# CPLD.net
KiCad netlist of a schematic drawn in Altium Designer
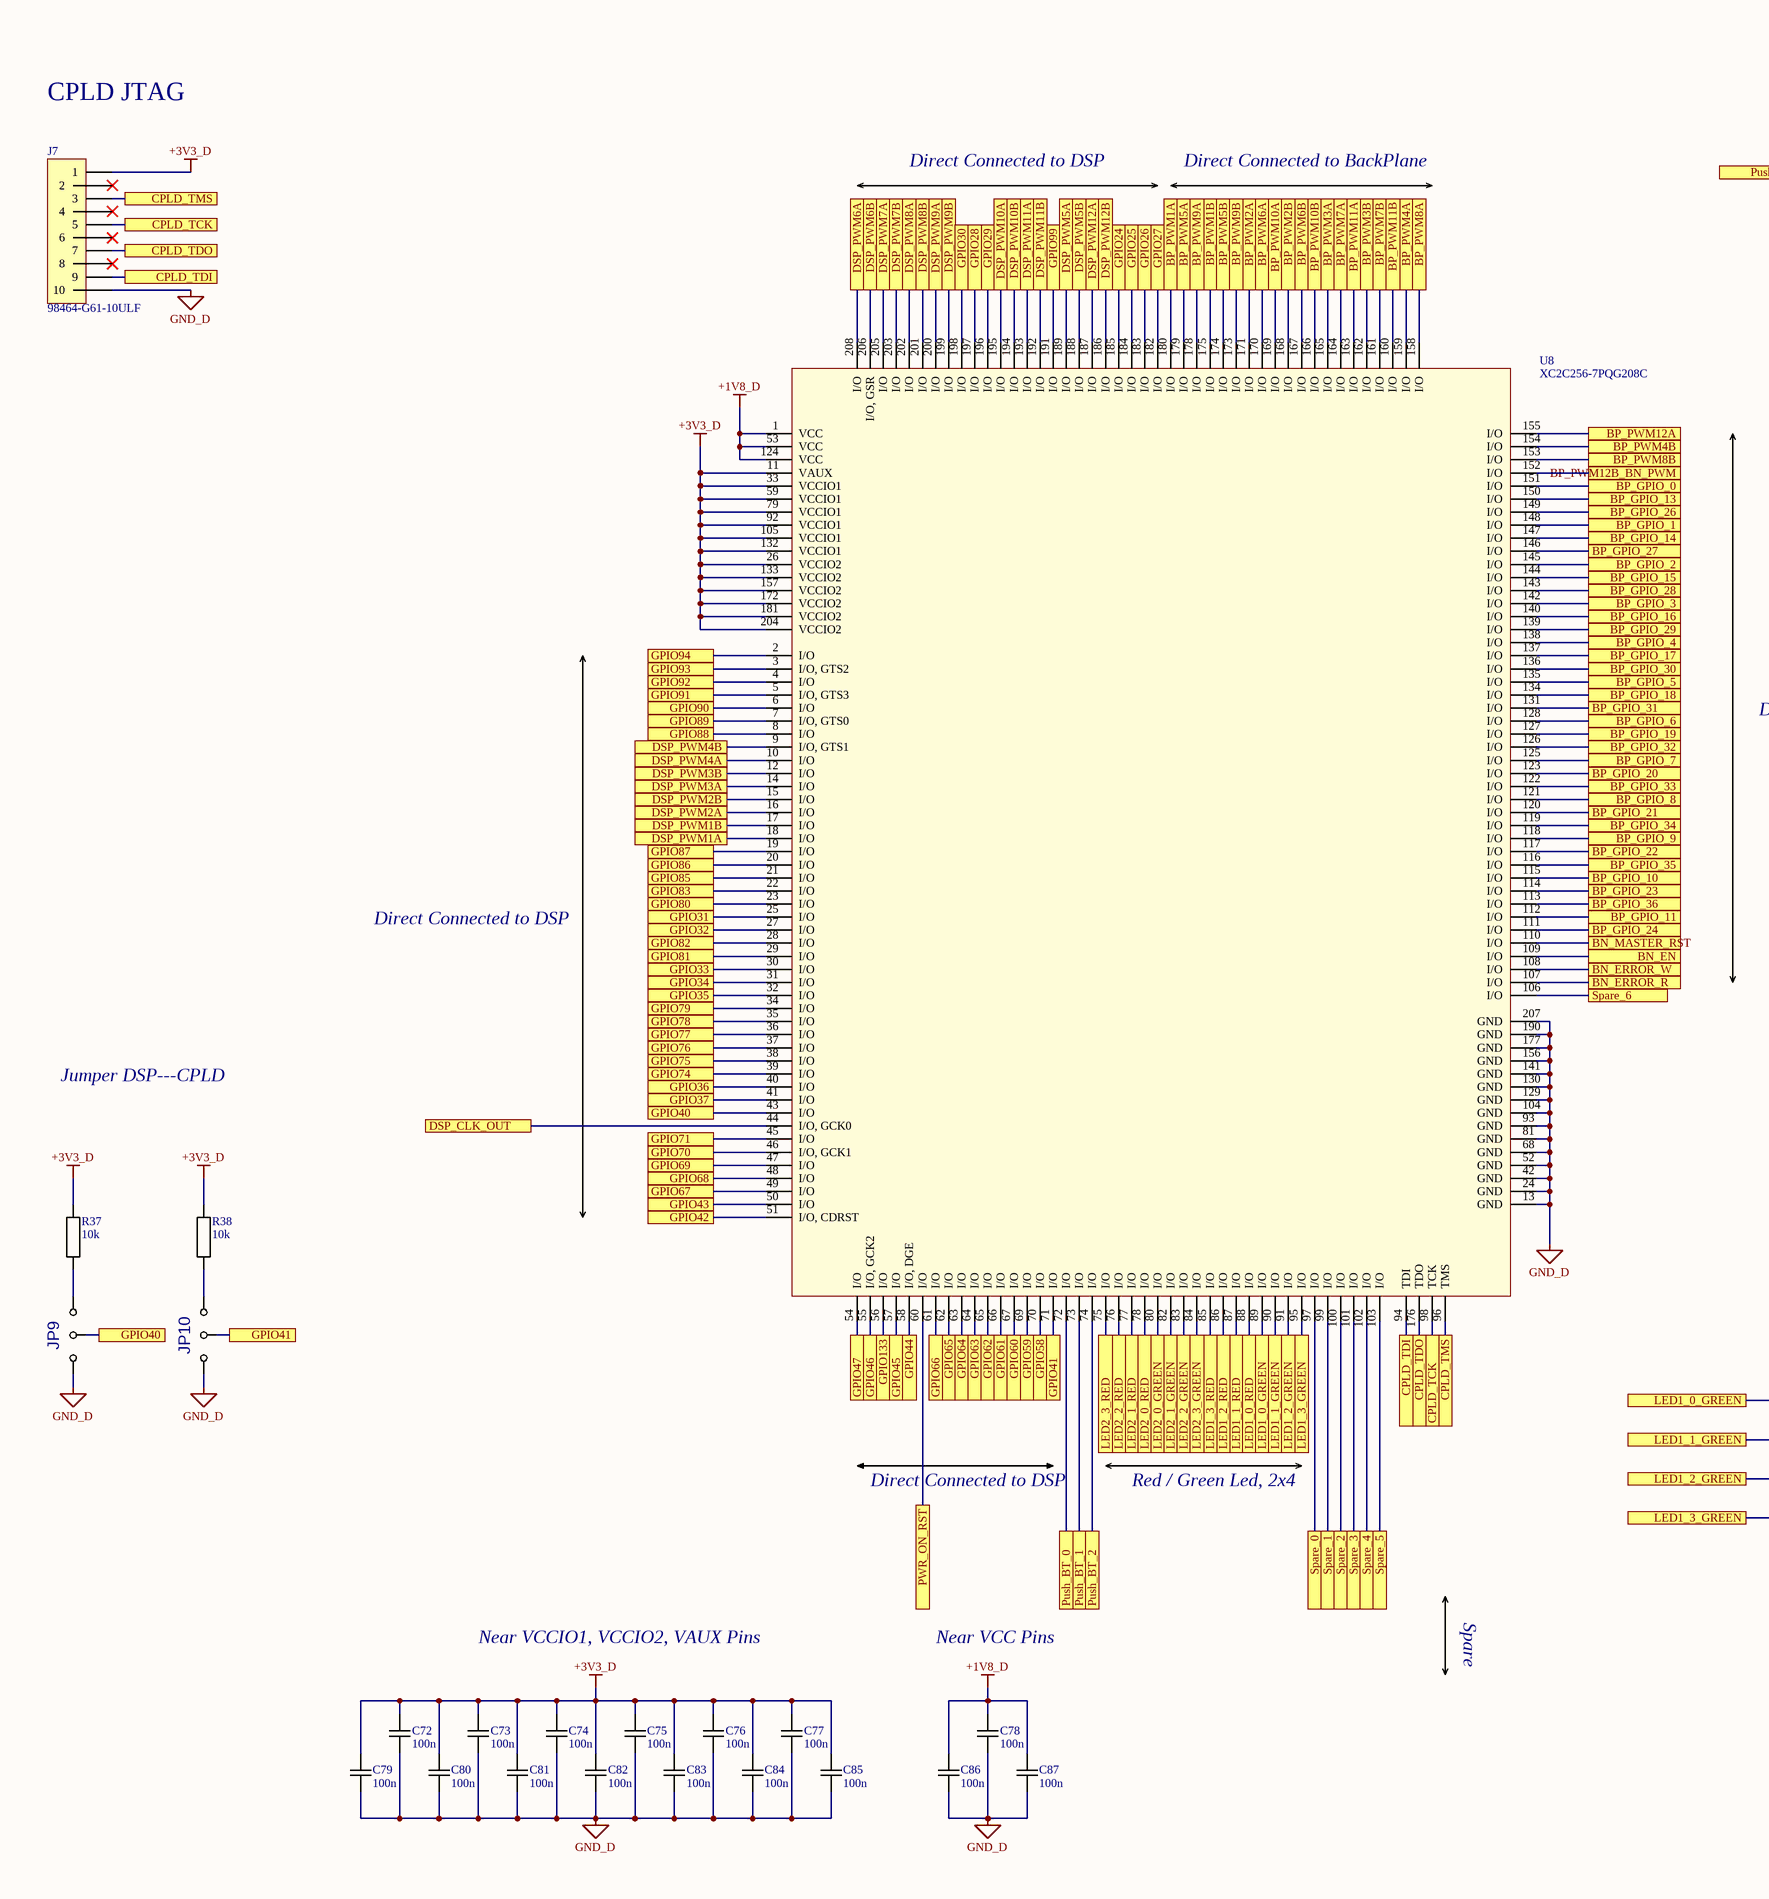
[diagram p0: CPLD.SchDoc, left]
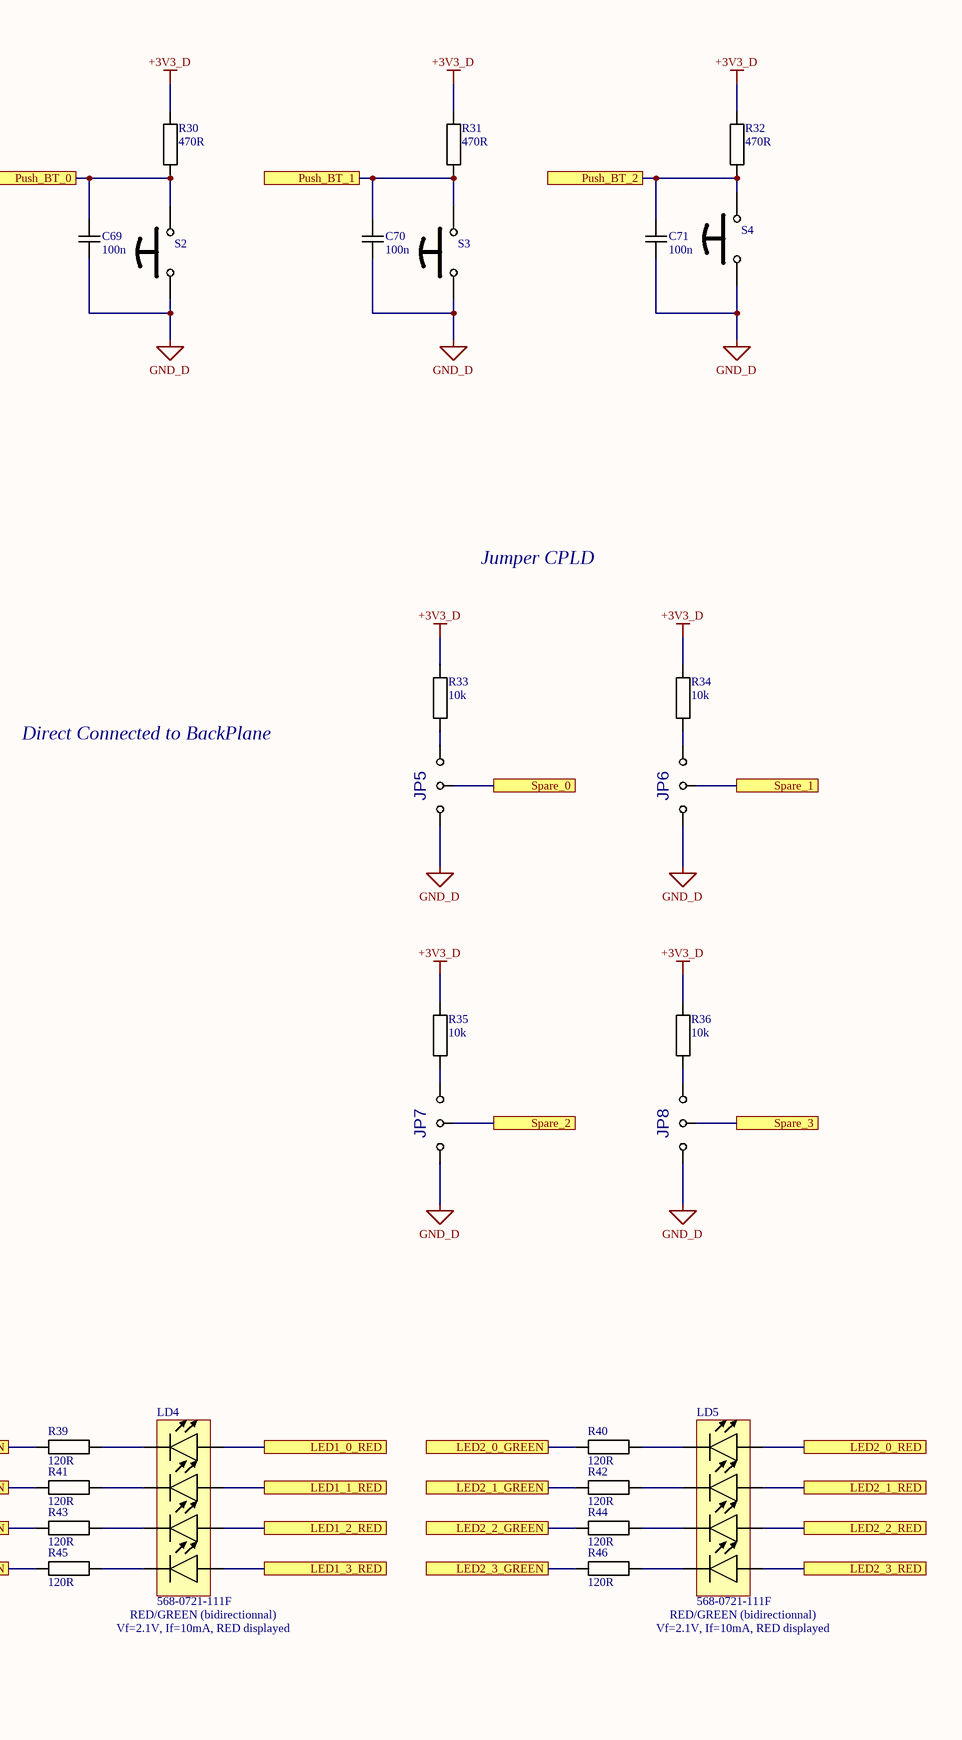
[diagram p1: CPLD.SchDoc, right]

(export (version "E")
  (design (tool "Eeschema 10.0.6"))
  (components
    (comp (ref "C69")
      (value "100n")
      (footprint "CAPACITOR 2012 REFLOW")
      (description "Capacitor X7R 10% 50V 2012(0805)")
      (libsource (lib "Capacitor") (part "Capacitor"))
    )
    (comp (ref "C70")
      (value "100n")
      (footprint "CAPACITOR 2012 REFLOW")
      (description "Capacitor X7R 10% 50V 2012(0805)")
      (libsource (lib "Capacitor") (part "Capacitor"))
    )
    (comp (ref "C71")
      (value "100n")
      (footprint "CAPACITOR 2012 REFLOW")
      (description "Capacitor X7R 10% 50V 2012(0805)")
      (libsource (lib "Capacitor") (part "Capacitor"))
    )
    (comp (ref "C72")
      (value "100n")
      (footprint "CAPACITOR 1608 REFLOW")
      (description "Capacitor X7R 10% 50V 1608(0603)")
      (libsource (lib "Capacitor") (part "Capacitor"))
    )
    (comp (ref "C73")
      (value "100n")
      (footprint "CAPACITOR 1608 REFLOW")
      (description "Capacitor X7R 10% 50V 1608(0603)")
      (libsource (lib "Capacitor") (part "Capacitor"))
    )
    (comp (ref "C74")
      (value "100n")
      (footprint "CAPACITOR 1608 REFLOW")
      (description "Capacitor X7R 10% 50V 1608(0603)")
      (libsource (lib "Capacitor") (part "Capacitor"))
    )
    (comp (ref "C75")
      (value "100n")
      (footprint "CAPACITOR 1608 REFLOW")
      (description "Capacitor X7R 10% 50V 1608(0603)")
      (libsource (lib "Capacitor") (part "Capacitor"))
    )
    (comp (ref "C76")
      (value "100n")
      (footprint "CAPACITOR 1608 REFLOW")
      (description "Capacitor X7R 10% 50V 1608(0603)")
      (libsource (lib "Capacitor") (part "Capacitor"))
    )
    (comp (ref "C77")
      (value "100n")
      (footprint "CAPACITOR 1608 REFLOW")
      (description "Capacitor X7R 10% 50V 1608(0603)")
      (libsource (lib "Capacitor") (part "Capacitor"))
    )
    (comp (ref "C78")
      (value "100n")
      (footprint "CAPACITOR 1608 REFLOW")
      (description "Capacitor X7R 10% 50V 1608(0603)")
      (libsource (lib "Capacitor") (part "Capacitor"))
    )
    (comp (ref "C79")
      (value "100n")
      (footprint "CAPACITOR 1608 REFLOW")
      (description "Capacitor X7R 10% 50V 1608(0603)")
      (libsource (lib "Capacitor") (part "Capacitor"))
    )
    (comp (ref "C80")
      (value "100n")
      (footprint "CAPACITOR 1608 REFLOW")
      (description "Capacitor X7R 10% 50V 1608(0603)")
      (libsource (lib "Capacitor") (part "Capacitor"))
    )
    (comp (ref "C81")
      (value "100n")
      (footprint "CAPACITOR 1608 REFLOW")
      (description "Capacitor X7R 10% 50V 1608(0603)")
      (libsource (lib "Capacitor") (part "Capacitor"))
    )
    (comp (ref "C82")
      (value "100n")
      (footprint "CAPACITOR 1608 REFLOW")
      (description "Capacitor X7R 10% 50V 1608(0603)")
      (libsource (lib "Capacitor") (part "Capacitor"))
    )
    (comp (ref "C83")
      (value "100n")
      (footprint "CAPACITOR 1608 REFLOW")
      (description "Capacitor X7R 10% 50V 1608(0603)")
      (libsource (lib "Capacitor") (part "Capacitor"))
    )
    (comp (ref "C84")
      (value "100n")
      (footprint "CAPACITOR 1608 REFLOW")
      (description "Capacitor X7R 10% 50V 1608(0603)")
      (libsource (lib "Capacitor") (part "Capacitor"))
    )
    (comp (ref "C85")
      (value "100n")
      (footprint "CAPACITOR 1608 REFLOW")
      (description "Capacitor X7R 10% 50V 1608(0603)")
      (libsource (lib "Capacitor") (part "Capacitor"))
    )
    (comp (ref "C86")
      (value "100n")
      (footprint "CAPACITOR 1608 REFLOW")
      (description "Capacitor X7R 10% 50V 1608(0603)")
      (libsource (lib "Capacitor") (part "Capacitor"))
    )
    (comp (ref "C87")
      (value "100n")
      (footprint "CAPACITOR 1608 REFLOW")
      (description "Capacitor X7R 10% 50V 1608(0603)")
      (libsource (lib "Capacitor") (part "Capacitor"))
    )
    (comp (ref "J7")
      (value "98464-G61-10ULF")
      (footprint "FlatCable2x5 2MM Right Angle TH FCI 98614-G61-10ULF")
      (description "FlatCable2x5")
      (fields (field (name "MANUFACTURER") "Amphenol FCI"))
      (libsource (lib "Connector") (part "FlatCable2x5"))
    )
    (comp (ref "JP5")
      (value "{Value}")
      (footprint "JUMPER3 TH")
      (description "JUMPER 3 POS")
      (libsource (lib "Jumper") (part "JUMPER 3 POS"))
    )
    (comp (ref "JP6")
      (value "{Value}")
      (footprint "JUMPER3 TH")
      (description "JUMPER 3 POS")
      (libsource (lib "Jumper") (part "JUMPER 3 POS"))
    )
    (comp (ref "JP7")
      (value "{Value}")
      (footprint "JUMPER3 TH")
      (description "JUMPER 3 POS")
      (libsource (lib "Jumper") (part "JUMPER 3 POS"))
    )
    (comp (ref "JP8")
      (value "{Value}")
      (footprint "JUMPER3 TH")
      (description "JUMPER 3 POS")
      (libsource (lib "Jumper") (part "JUMPER 3 POS"))
    )
    (comp (ref "JP9")
      (value "{Value}")
      (footprint "JUMPER3 TH")
      (description "JUMPER 3 POS")
      (libsource (lib "Jumper") (part "JUMPER 3 POS"))
    )
    (comp (ref "JP10")
      (value "{Value}")
      (footprint "JUMPER3 TH")
      (description "JUMPER 3 POS")
      (libsource (lib "Jumper") (part "JUMPER 3 POS"))
    )
    (comp (ref "LD4")
      (value "568-0721-111F")
      (footprint "LED Dialight 568-0721-111")
      (description "LED Dialight 568-0721-111F")
      (fields (field (name "MANUFACTURER") "Dialight"))
      (libsource (lib "Diode") (part "LED Dialight 568-0721-111F"))
    )
    (comp (ref "LD5")
      (value "568-0721-111F")
      (footprint "LED Dialight 568-0721-111")
      (description "LED Dialight 568-0721-111F")
      (fields (field (name "MANUFACTURER") "Dialight"))
      (libsource (lib "Diode") (part "LED Dialight 568-0721-111F"))
    )
    (comp (ref "R30")
      (value "470R")
      (footprint "RESISTOR 2012 REFLOW")
      (description "Resistor 1% 50V 125mW 2012(0805)")
      (libsource (lib "Resistor") (part "Resistor"))
    )
    (comp (ref "R31")
      (value "470R")
      (footprint "RESISTOR 2012 REFLOW")
      (description "Resistor 1% 50V 125mW 2012(0805)")
      (libsource (lib "Resistor") (part "Resistor"))
    )
    (comp (ref "R32")
      (value "470R")
      (footprint "RESISTOR 2012 REFLOW")
      (description "Resistor 1% 50V 125mW 2012(0805)")
      (libsource (lib "Resistor") (part "Resistor"))
    )
    (comp (ref "R33")
      (value "10k")
      (footprint "RESISTOR 2012 REFLOW")
      (description "Resistor 1% 50V 125mW 2012(0805)")
      (libsource (lib "Resistor") (part "Resistor"))
    )
    (comp (ref "R34")
      (value "10k")
      (footprint "RESISTOR 2012 REFLOW")
      (description "Resistor 1% 50V 125mW 2012(0805)")
      (libsource (lib "Resistor") (part "Resistor"))
    )
    (comp (ref "R35")
      (value "10k")
      (footprint "RESISTOR 2012 REFLOW")
      (description "Resistor 1% 50V 125mW 2012(0805)")
      (libsource (lib "Resistor") (part "Resistor"))
    )
    (comp (ref "R36")
      (value "10k")
      (footprint "RESISTOR 2012 REFLOW")
      (description "Resistor 1% 50V 125mW 2012(0805)")
      (libsource (lib "Resistor") (part "Resistor"))
    )
    (comp (ref "R37")
      (value "10k")
      (footprint "RESISTOR 2012 REFLOW")
      (description "Resistor 1% 50V 125mW 2012(0805)")
      (libsource (lib "Resistor") (part "Resistor"))
    )
    (comp (ref "R38")
      (value "10k")
      (footprint "RESISTOR 2012 REFLOW")
      (description "Resistor 1% 50V 125mW 2012(0805)")
      (libsource (lib "Resistor") (part "Resistor"))
    )
    (comp (ref "R39")
      (value "120R")
      (footprint "RESISTOR 1608 REFLOW")
      (description "Resistor 1% 50V 100mW 1608(0603)")
      (libsource (lib "Resistor") (part "Resistor"))
    )
    (comp (ref "R40")
      (value "120R")
      (footprint "RESISTOR 1608 REFLOW")
      (description "Resistor 1% 50V 100mW 1608(0603)")
      (libsource (lib "Resistor") (part "Resistor"))
    )
    (comp (ref "R41")
      (value "120R")
      (footprint "RESISTOR 1608 REFLOW")
      (description "Resistor 1% 50V 100mW 1608(0603)")
      (libsource (lib "Resistor") (part "Resistor"))
    )
    (comp (ref "R42")
      (value "120R")
      (footprint "RESISTOR 1608 REFLOW")
      (description "Resistor 1% 50V 100mW 1608(0603)")
      (libsource (lib "Resistor") (part "Resistor"))
    )
    (comp (ref "R43")
      (value "120R")
      (footprint "RESISTOR 1608 REFLOW")
      (description "Resistor 1% 50V 100mW 1608(0603)")
      (libsource (lib "Resistor") (part "Resistor"))
    )
    (comp (ref "R44")
      (value "120R")
      (footprint "RESISTOR 1608 REFLOW")
      (description "Resistor 1% 50V 100mW 1608(0603)")
      (libsource (lib "Resistor") (part "Resistor"))
    )
    (comp (ref "R45")
      (value "120R")
      (footprint "RESISTOR 1608 REFLOW")
      (description "Resistor 1% 50V 100mW 1608(0603)")
      (libsource (lib "Resistor") (part "Resistor"))
    )
    (comp (ref "R46")
      (value "120R")
      (footprint "RESISTOR 1608 REFLOW")
      (description "Resistor 1% 50V 100mW 1608(0603)")
      (libsource (lib "Resistor") (part "Resistor"))
    )
    (comp (ref "S2")
      (value "FSMRA4JH04")
      (footprint "Push Button C7.1x3.7 TE FSMRA4JH")
      (description "Push Button, 2 pins")
      (fields (field (name "MANUFACTURER") "TE Connectivity / Alcoswitch"))
      (libsource (lib "Button") (part "Push Button 2Pins"))
    )
    (comp (ref "S3")
      (value "FSMRA4JH04")
      (footprint "Push Button C7.1x3.7 TE FSMRA4JH")
      (description "Push Button, 2 pins")
      (fields (field (name "MANUFACTURER") "TE Connectivity / Alcoswitch"))
      (libsource (lib "Button") (part "Push Button 2Pins"))
    )
    (comp (ref "S4")
      (value "FSMRA4JH04")
      (footprint "Push Button C7.1x3.7 TE FSMRA4JH")
      (description "Push Button, 2 pins")
      (fields (field (name "MANUFACTURER") "TE Connectivity / Alcoswitch"))
      (libsource (lib "Button") (part "Push Button 2Pins"))
    )
    (comp (ref "U8")
      (value "XC2C256-7PQG208C")
      (footprint "PQFP208 P0.5 C28.0X28.0 H3.7")
      (description "XC2C256 CoolRunner-II CPLD")
      (fields (field (name "MANUFACTURER") "Xilinx"))
      (libsource (lib "Processor") (part "XC2C256-PQFP208"))
    )
  )
  (nets
    (net (code "1") (name "+1V8_D") (class "Default")
      (node (ref "C78") (pin "2") (pinfunction "2_2") (pintype "passive"))
      (node (ref "C86") (pin "2") (pinfunction "2_2") (pintype "passive"))
      (node (ref "C87") (pin "2") (pinfunction "2_2") (pintype "passive"))
      (node (ref "U8") (pin "1") (pinfunction "VCC_1") (pintype "passive"))
      (node (ref "U8") (pin "124") (pinfunction "VCC_124") (pintype "passive"))
      (node (ref "U8") (pin "53") (pinfunction "VCC_53") (pintype "passive"))
    )
    (net (code "2") (name "+3V3_D") (class "Default")
      (node (ref "C72") (pin "2") (pinfunction "2_2") (pintype "passive"))
      (node (ref "C73") (pin "2") (pinfunction "2_2") (pintype "passive"))
      (node (ref "C74") (pin "2") (pinfunction "2_2") (pintype "passive"))
      (node (ref "C75") (pin "2") (pinfunction "2_2") (pintype "passive"))
      (node (ref "C76") (pin "2") (pinfunction "2_2") (pintype "passive"))
      (node (ref "C77") (pin "2") (pinfunction "2_2") (pintype "passive"))
      (node (ref "C79") (pin "2") (pinfunction "2_2") (pintype "passive"))
      (node (ref "C80") (pin "2") (pinfunction "2_2") (pintype "passive"))
      (node (ref "C81") (pin "2") (pinfunction "2_2") (pintype "passive"))
      (node (ref "C82") (pin "2") (pinfunction "2_2") (pintype "passive"))
      (node (ref "C83") (pin "2") (pinfunction "2_2") (pintype "passive"))
      (node (ref "C84") (pin "2") (pinfunction "2_2") (pintype "passive"))
      (node (ref "C85") (pin "2") (pinfunction "2_2") (pintype "passive"))
      (node (ref "J7") (pin "1") (pinfunction "1_1") (pintype "passive"))
      (node (ref "R30") (pin "2") (pinfunction "2_2") (pintype "passive"))
      (node (ref "R31") (pin "2") (pinfunction "2_2") (pintype "passive"))
      (node (ref "R32") (pin "2") (pinfunction "2_2") (pintype "passive"))
      (node (ref "R33") (pin "2") (pinfunction "2_2") (pintype "passive"))
      (node (ref "R34") (pin "2") (pinfunction "2_2") (pintype "passive"))
      (node (ref "R35") (pin "2") (pinfunction "2_2") (pintype "passive"))
      (node (ref "R36") (pin "2") (pinfunction "2_2") (pintype "passive"))
      (node (ref "R37") (pin "1") (pinfunction "1_1") (pintype "passive"))
      (node (ref "R38") (pin "1") (pinfunction "1_1") (pintype "passive"))
      (node (ref "U8") (pin "105") (pinfunction "VCCIO1_105") (pintype "passive"))
      (node (ref "U8") (pin "11") (pinfunction "VAUX_11") (pintype "passive"))
      (node (ref "U8") (pin "132") (pinfunction "VCCIO1_132") (pintype "passive"))
      (node (ref "U8") (pin "133") (pinfunction "VCCIO2_133") (pintype "passive"))
      (node (ref "U8") (pin "157") (pinfunction "VCCIO2_157") (pintype "passive"))
      (node (ref "U8") (pin "172") (pinfunction "VCCIO2_172") (pintype "passive"))
      (node (ref "U8") (pin "181") (pinfunction "VCCIO2_181") (pintype "passive"))
      (node (ref "U8") (pin "204") (pinfunction "VCCIO2_204") (pintype "passive"))
      (node (ref "U8") (pin "26") (pinfunction "VCCIO2_26") (pintype "passive"))
      (node (ref "U8") (pin "33") (pinfunction "VCCIO1_33") (pintype "passive"))
      (node (ref "U8") (pin "59") (pinfunction "VCCIO1_59") (pintype "passive"))
      (node (ref "U8") (pin "79") (pinfunction "VCCIO1_79") (pintype "passive"))
      (node (ref "U8") (pin "92") (pinfunction "VCCIO1_92") (pintype "passive"))
    )
    (net (code "3") (name "/BN_EN") (class "Default")
      (node (ref "U8") (pin "109") (pinfunction "I/O_109") (pintype "passive"))
    )
    (net (code "4") (name "/BN_ERROR_R") (class "Default")
      (node (ref "U8") (pin "107") (pinfunction "I/O_107") (pintype "passive"))
    )
    (net (code "5") (name "/BN_ERROR_W") (class "Default")
      (node (ref "U8") (pin "108") (pinfunction "I/O_108") (pintype "passive"))
    )
    (net (code "6") (name "/BN_MASTER_RST") (class "Default")
      (node (ref "U8") (pin "110") (pinfunction "I/O_110") (pintype "passive"))
    )
    (net (code "7") (name "/BP_GPIO_0") (class "Default")
      (node (ref "U8") (pin "151") (pinfunction "I/O_151") (pintype "passive"))
    )
    (net (code "8") (name "/BP_GPIO_1") (class "Default")
      (node (ref "U8") (pin "148") (pinfunction "I/O_148") (pintype "passive"))
    )
    (net (code "9") (name "/BP_GPIO_2") (class "Default")
      (node (ref "U8") (pin "145") (pinfunction "I/O_145") (pintype "passive"))
    )
    (net (code "10") (name "/BP_GPIO_3") (class "Default")
      (node (ref "U8") (pin "142") (pinfunction "I/O_142") (pintype "passive"))
    )
    (net (code "11") (name "/BP_GPIO_4") (class "Default")
      (node (ref "U8") (pin "138") (pinfunction "I/O_138") (pintype "passive"))
    )
    (net (code "12") (name "/BP_GPIO_5") (class "Default")
      (node (ref "U8") (pin "135") (pinfunction "I/O_135") (pintype "passive"))
    )
    (net (code "13") (name "/BP_GPIO_6") (class "Default")
      (node (ref "U8") (pin "128") (pinfunction "I/O_128") (pintype "passive"))
    )
    (net (code "14") (name "/BP_GPIO_7") (class "Default")
      (node (ref "U8") (pin "125") (pinfunction "I/O_125") (pintype "passive"))
    )
    (net (code "15") (name "/BP_GPIO_8") (class "Default")
      (node (ref "U8") (pin "121") (pinfunction "I/O_121") (pintype "passive"))
    )
    (net (code "16") (name "/BP_GPIO_9") (class "Default")
      (node (ref "U8") (pin "118") (pinfunction "I/O_118") (pintype "passive"))
    )
    (net (code "17") (name "/BP_GPIO_10") (class "Default")
      (node (ref "U8") (pin "115") (pinfunction "I/O_115") (pintype "passive"))
    )
    (net (code "18") (name "/BP_GPIO_11") (class "Default")
      (node (ref "U8") (pin "112") (pinfunction "I/O_112") (pintype "passive"))
    )
    (net (code "19") (name "/BP_GPIO_13") (class "Default")
      (node (ref "U8") (pin "150") (pinfunction "I/O_150") (pintype "passive"))
    )
    (net (code "20") (name "/BP_GPIO_14") (class "Default")
      (node (ref "U8") (pin "147") (pinfunction "I/O_147") (pintype "passive"))
    )
    (net (code "21") (name "/BP_GPIO_15") (class "Default")
      (node (ref "U8") (pin "144") (pinfunction "I/O_144") (pintype "passive"))
    )
    (net (code "22") (name "/BP_GPIO_16") (class "Default")
      (node (ref "U8") (pin "140") (pinfunction "I/O_140") (pintype "passive"))
    )
    (net (code "23") (name "/BP_GPIO_17") (class "Default")
      (node (ref "U8") (pin "137") (pinfunction "I/O_137") (pintype "passive"))
    )
    (net (code "24") (name "/BP_GPIO_18") (class "Default")
      (node (ref "U8") (pin "134") (pinfunction "I/O_134") (pintype "passive"))
    )
    (net (code "25") (name "/BP_GPIO_19") (class "Default")
      (node (ref "U8") (pin "127") (pinfunction "I/O_127") (pintype "passive"))
    )
    (net (code "26") (name "/BP_GPIO_20") (class "Default")
      (node (ref "U8") (pin "123") (pinfunction "I/O_123") (pintype "passive"))
    )
    (net (code "27") (name "/BP_GPIO_21") (class "Default")
      (node (ref "U8") (pin "120") (pinfunction "I/O_120") (pintype "passive"))
    )
    (net (code "28") (name "/BP_GPIO_22") (class "Default")
      (node (ref "U8") (pin "117") (pinfunction "I/O_117") (pintype "passive"))
    )
    (net (code "29") (name "/BP_GPIO_23") (class "Default")
      (node (ref "U8") (pin "114") (pinfunction "I/O_114") (pintype "passive"))
    )
    (net (code "30") (name "/BP_GPIO_24") (class "Default")
      (node (ref "U8") (pin "111") (pinfunction "I/O_111") (pintype "passive"))
    )
    (net (code "31") (name "/BP_GPIO_26") (class "Default")
      (node (ref "U8") (pin "149") (pinfunction "I/O_149") (pintype "passive"))
    )
    (net (code "32") (name "/BP_GPIO_27") (class "Default")
      (node (ref "U8") (pin "146") (pinfunction "I/O_146") (pintype "passive"))
    )
    (net (code "33") (name "/BP_GPIO_28") (class "Default")
      (node (ref "U8") (pin "143") (pinfunction "I/O_143") (pintype "passive"))
    )
    (net (code "34") (name "/BP_GPIO_29") (class "Default")
      (node (ref "U8") (pin "139") (pinfunction "I/O_139") (pintype "passive"))
    )
    (net (code "35") (name "/BP_GPIO_30") (class "Default")
      (node (ref "U8") (pin "136") (pinfunction "I/O_136") (pintype "passive"))
    )
    (net (code "36") (name "/BP_GPIO_31") (class "Default")
      (node (ref "U8") (pin "131") (pinfunction "I/O_131") (pintype "passive"))
    )
    (net (code "37") (name "/BP_GPIO_32") (class "Default")
      (node (ref "U8") (pin "126") (pinfunction "I/O_126") (pintype "passive"))
    )
    (net (code "38") (name "/BP_GPIO_33") (class "Default")
      (node (ref "U8") (pin "122") (pinfunction "I/O_122") (pintype "passive"))
    )
    (net (code "39") (name "/BP_GPIO_34") (class "Default")
      (node (ref "U8") (pin "119") (pinfunction "I/O_119") (pintype "passive"))
    )
    (net (code "40") (name "/BP_GPIO_35") (class "Default")
      (node (ref "U8") (pin "116") (pinfunction "I/O_116") (pintype "passive"))
    )
    (net (code "41") (name "/BP_GPIO_36") (class "Default")
      (node (ref "U8") (pin "113") (pinfunction "I/O_113") (pintype "passive"))
    )
    (net (code "42") (name "/BP_PWM1A") (class "Default")
      (node (ref "U8") (pin "180") (pinfunction "I/O_180") (pintype "passive"))
    )
    (net (code "43") (name "/BP_PWM1B") (class "Default")
      (node (ref "U8") (pin "175") (pinfunction "I/O_175") (pintype "passive"))
    )
    (net (code "44") (name "/BP_PWM2A") (class "Default")
      (node (ref "U8") (pin "171") (pinfunction "I/O_171") (pintype "passive"))
    )
    (net (code "45") (name "/BP_PWM2B") (class "Default")
      (node (ref "U8") (pin "168") (pinfunction "I/O_168") (pintype "passive"))
    )
    (net (code "46") (name "/BP_PWM3A") (class "Default")
      (node (ref "U8") (pin "165") (pinfunction "I/O_165") (pintype "passive"))
    )
    (net (code "47") (name "/BP_PWM3B") (class "Default")
      (node (ref "U8") (pin "162") (pinfunction "I/O_162") (pintype "passive"))
    )
    (net (code "48") (name "/BP_PWM4A") (class "Default")
      (node (ref "U8") (pin "159") (pinfunction "I/O_159") (pintype "passive"))
    )
    (net (code "49") (name "/BP_PWM4B") (class "Default")
      (node (ref "U8") (pin "154") (pinfunction "I/O_154") (pintype "passive"))
    )
    (net (code "50") (name "/BP_PWM5A") (class "Default")
      (node (ref "U8") (pin "179") (pinfunction "I/O_179") (pintype "passive"))
    )
    (net (code "51") (name "/BP_PWM5B") (class "Default")
      (node (ref "U8") (pin "174") (pinfunction "I/O_174") (pintype "passive"))
    )
    (net (code "52") (name "/BP_PWM6A") (class "Default")
      (node (ref "U8") (pin "170") (pinfunction "I/O_170") (pintype "passive"))
    )
    (net (code "53") (name "/BP_PWM6B") (class "Default")
      (node (ref "U8") (pin "167") (pinfunction "I/O_167") (pintype "passive"))
    )
    (net (code "54") (name "/BP_PWM7A") (class "Default")
      (node (ref "U8") (pin "164") (pinfunction "I/O_164") (pintype "passive"))
    )
    (net (code "55") (name "/BP_PWM7B") (class "Default")
      (node (ref "U8") (pin "161") (pinfunction "I/O_161") (pintype "passive"))
    )
    (net (code "56") (name "/BP_PWM8A") (class "Default")
      (node (ref "U8") (pin "158") (pinfunction "I/O_158") (pintype "passive"))
    )
    (net (code "57") (name "/BP_PWM8B") (class "Default")
      (node (ref "U8") (pin "153") (pinfunction "I/O_153") (pintype "passive"))
    )
    (net (code "58") (name "/BP_PWM9A") (class "Default")
      (node (ref "U8") (pin "178") (pinfunction "I/O_178") (pintype "passive"))
    )
    (net (code "59") (name "/BP_PWM9B") (class "Default")
      (node (ref "U8") (pin "173") (pinfunction "I/O_173") (pintype "passive"))
    )
    (net (code "60") (name "/BP_PWM10A") (class "Default")
      (node (ref "U8") (pin "169") (pinfunction "I/O_169") (pintype "passive"))
    )
    (net (code "61") (name "/BP_PWM10B") (class "Default")
      (node (ref "U8") (pin "166") (pinfunction "I/O_166") (pintype "passive"))
    )
    (net (code "62") (name "/BP_PWM11A") (class "Default")
      (node (ref "U8") (pin "163") (pinfunction "I/O_163") (pintype "passive"))
    )
    (net (code "63") (name "/BP_PWM11B") (class "Default")
      (node (ref "U8") (pin "160") (pinfunction "I/O_160") (pintype "passive"))
    )
    (net (code "64") (name "/BP_PWM12A") (class "Default")
      (node (ref "U8") (pin "155") (pinfunction "I/O_155") (pintype "passive"))
    )
    (net (code "65") (name "/BP_PWM12B_BN_PWM") (class "Default")
      (node (ref "U8") (pin "152") (pinfunction "I/O_152") (pintype "passive"))
    )
    (net (code "66") (name "/CPLD_TCK") (class "Default")
      (node (ref "J7") (pin "5") (pinfunction "5_5") (pintype "passive"))
      (node (ref "U8") (pin "98") (pinfunction "TCK_98") (pintype "passive"))
    )
    (net (code "67") (name "/CPLD_TDI") (class "Default")
      (node (ref "J7") (pin "9") (pinfunction "9_9") (pintype "passive"))
      (node (ref "U8") (pin "94") (pinfunction "TDI_94") (pintype "passive"))
    )
    (net (code "68") (name "/CPLD_TDO") (class "Default")
      (node (ref "J7") (pin "7") (pinfunction "7_7") (pintype "passive"))
      (node (ref "U8") (pin "176") (pinfunction "TDO_176") (pintype "passive"))
    )
    (net (code "69") (name "/CPLD_TMS") (class "Default")
      (node (ref "J7") (pin "3") (pinfunction "3_3") (pintype "passive"))
      (node (ref "U8") (pin "96") (pinfunction "TMS_96") (pintype "passive"))
    )
    (net (code "70") (name "/DSP_CLK_OUT") (class "Default")
      (node (ref "U8") (pin "44") (pinfunction "I/O,_GCK0_44") (pintype "passive"))
    )
    (net (code "71") (name "/DSP_PWM1A") (class "Default")
      (node (ref "U8") (pin "18") (pinfunction "I/O_18") (pintype "passive"))
    )
    (net (code "72") (name "/DSP_PWM1B") (class "Default")
      (node (ref "U8") (pin "17") (pinfunction "I/O_17") (pintype "passive"))
    )
    (net (code "73") (name "/DSP_PWM2A") (class "Default")
      (node (ref "U8") (pin "16") (pinfunction "I/O_16") (pintype "passive"))
    )
    (net (code "74") (name "/DSP_PWM2B") (class "Default")
      (node (ref "U8") (pin "15") (pinfunction "I/O_15") (pintype "passive"))
    )
    (net (code "75") (name "/DSP_PWM3A") (class "Default")
      (node (ref "U8") (pin "14") (pinfunction "I/O_14") (pintype "passive"))
    )
    (net (code "76") (name "/DSP_PWM3B") (class "Default")
      (node (ref "U8") (pin "12") (pinfunction "I/O_12") (pintype "passive"))
    )
    (net (code "77") (name "/DSP_PWM4A") (class "Default")
      (node (ref "U8") (pin "10") (pinfunction "I/O_10") (pintype "passive"))
    )
    (net (code "78") (name "/DSP_PWM4B") (class "Default")
      (node (ref "U8") (pin "9") (pinfunction "I/O,_GTS1_9") (pintype "passive"))
    )
    (net (code "79") (name "/DSP_PWM5A") (class "Default")
      (node (ref "U8") (pin "189") (pinfunction "I/O_189") (pintype "passive"))
    )
    (net (code "80") (name "/DSP_PWM5B") (class "Default")
      (node (ref "U8") (pin "188") (pinfunction "I/O_188") (pintype "passive"))
    )
    (net (code "81") (name "/DSP_PWM6A") (class "Default")
      (node (ref "U8") (pin "208") (pinfunction "I/O_208") (pintype "passive"))
    )
    (net (code "82") (name "/DSP_PWM6B") (class "Default")
      (node (ref "U8") (pin "206") (pinfunction "I/O,_GSR_206") (pintype "passive"))
    )
    (net (code "83") (name "/DSP_PWM7A") (class "Default")
      (node (ref "U8") (pin "205") (pinfunction "I/O_205") (pintype "passive"))
    )
    (net (code "84") (name "/DSP_PWM7B") (class "Default")
      (node (ref "U8") (pin "203") (pinfunction "I/O_203") (pintype "passive"))
    )
    (net (code "85") (name "/DSP_PWM8A") (class "Default")
      (node (ref "U8") (pin "202") (pinfunction "I/O_202") (pintype "passive"))
    )
    (net (code "86") (name "/DSP_PWM8B") (class "Default")
      (node (ref "U8") (pin "201") (pinfunction "I/O_201") (pintype "passive"))
    )
    (net (code "87") (name "/DSP_PWM9A") (class "Default")
      (node (ref "U8") (pin "200") (pinfunction "I/O_200") (pintype "passive"))
    )
    (net (code "88") (name "/DSP_PWM9B") (class "Default")
      (node (ref "U8") (pin "199") (pinfunction "I/O_199") (pintype "passive"))
    )
    (net (code "89") (name "/DSP_PWM10A") (class "Default")
      (node (ref "U8") (pin "195") (pinfunction "I/O_195") (pintype "passive"))
    )
    (net (code "90") (name "/DSP_PWM10B") (class "Default")
      (node (ref "U8") (pin "194") (pinfunction "I/O_194") (pintype "passive"))
    )
    (net (code "91") (name "/DSP_PWM11A") (class "Default")
      (node (ref "U8") (pin "193") (pinfunction "I/O_193") (pintype "passive"))
    )
    (net (code "92") (name "/DSP_PWM11B") (class "Default")
      (node (ref "U8") (pin "192") (pinfunction "I/O_192") (pintype "passive"))
    )
    (net (code "93") (name "/DSP_PWM12A") (class "Default")
      (node (ref "U8") (pin "187") (pinfunction "I/O_187") (pintype "passive"))
    )
    (net (code "94") (name "/DSP_PWM12B") (class "Default")
      (node (ref "U8") (pin "186") (pinfunction "I/O_186") (pintype "passive"))
    )
    (net (code "95") (name "/GPIO24") (class "Default")
      (node (ref "U8") (pin "185") (pinfunction "I/O_185") (pintype "passive"))
    )
    (net (code "96") (name "/GPIO25") (class "Default")
      (node (ref "U8") (pin "184") (pinfunction "I/O_184") (pintype "passive"))
    )
    (net (code "97") (name "/GPIO26") (class "Default")
      (node (ref "U8") (pin "183") (pinfunction "I/O_183") (pintype "passive"))
    )
    (net (code "98") (name "/GPIO27") (class "Default")
      (node (ref "U8") (pin "182") (pinfunction "I/O_182") (pintype "passive"))
    )
    (net (code "99") (name "/GPIO28") (class "Default")
      (node (ref "U8") (pin "197") (pinfunction "I/O_197") (pintype "passive"))
    )
    (net (code "100") (name "/GPIO29") (class "Default")
      (node (ref "U8") (pin "196") (pinfunction "I/O_196") (pintype "passive"))
    )
    (net (code "101") (name "/GPIO30") (class "Default")
      (node (ref "U8") (pin "198") (pinfunction "I/O_198") (pintype "passive"))
    )
    (net (code "102") (name "/GPIO31") (class "Default")
      (node (ref "U8") (pin "25") (pinfunction "I/O_25") (pintype "passive"))
    )
    (net (code "103") (name "/GPIO32") (class "Default")
      (node (ref "U8") (pin "27") (pinfunction "I/O_27") (pintype "passive"))
    )
    (net (code "104") (name "/GPIO33") (class "Default")
      (node (ref "U8") (pin "30") (pinfunction "I/O_30") (pintype "passive"))
    )
    (net (code "105") (name "/GPIO34") (class "Default")
      (node (ref "U8") (pin "31") (pinfunction "I/O_31") (pintype "passive"))
    )
    (net (code "106") (name "/GPIO35") (class "Default")
      (node (ref "U8") (pin "32") (pinfunction "I/O_32") (pintype "passive"))
    )
    (net (code "107") (name "/GPIO36") (class "Default")
      (node (ref "U8") (pin "40") (pinfunction "I/O_40") (pintype "passive"))
    )
    (net (code "108") (name "/GPIO37") (class "Default")
      (node (ref "U8") (pin "41") (pinfunction "I/O_41") (pintype "passive"))
    )
    (net (code "109") (name "/GPIO40") (class "Default")
      (node (ref "JP9") (pin "2") (pinfunction "2_2") (pintype "passive"))
      (node (ref "U8") (pin "43") (pinfunction "I/O_43") (pintype "passive"))
    )
    (net (code "110") (name "/GPIO41") (class "Default")
      (node (ref "JP10") (pin "2") (pinfunction "2_2") (pintype "passive"))
      (node (ref "U8") (pin "71") (pinfunction "I/O_71") (pintype "passive"))
    )
    (net (code "111") (name "/GPIO42") (class "Default")
      (node (ref "U8") (pin "51") (pinfunction "I/O,_CDRST_51") (pintype "passive"))
    )
    (net (code "112") (name "/GPIO43") (class "Default")
      (node (ref "U8") (pin "50") (pinfunction "I/O_50") (pintype "passive"))
    )
    (net (code "113") (name "/GPIO44") (class "Default")
      (node (ref "U8") (pin "58") (pinfunction "I/O,_DGE_58") (pintype "passive"))
    )
    (net (code "114") (name "/GPIO45") (class "Default")
      (node (ref "U8") (pin "57") (pinfunction "I/O_57") (pintype "passive"))
    )
    (net (code "115") (name "/GPIO46") (class "Default")
      (node (ref "U8") (pin "55") (pinfunction "I/O,_GCK2_55") (pintype "passive"))
    )
    (net (code "116") (name "/GPIO47") (class "Default")
      (node (ref "U8") (pin "54") (pinfunction "I/O_54") (pintype "passive"))
    )
    (net (code "117") (name "/GPIO58") (class "Default")
      (node (ref "U8") (pin "70") (pinfunction "I/O_70") (pintype "passive"))
    )
    (net (code "118") (name "/GPIO59") (class "Default")
      (node (ref "U8") (pin "69") (pinfunction "I/O_69") (pintype "passive"))
    )
    (net (code "119") (name "/GPIO60") (class "Default")
      (node (ref "U8") (pin "67") (pinfunction "I/O_67") (pintype "passive"))
    )
    (net (code "120") (name "/GPIO61") (class "Default")
      (node (ref "U8") (pin "66") (pinfunction "I/O_66") (pintype "passive"))
    )
    (net (code "121") (name "/GPIO62") (class "Default")
      (node (ref "U8") (pin "65") (pinfunction "I/O_65") (pintype "passive"))
    )
    (net (code "122") (name "/GPIO63") (class "Default")
      (node (ref "U8") (pin "64") (pinfunction "I/O_64") (pintype "passive"))
    )
    (net (code "123") (name "/GPIO64") (class "Default")
      (node (ref "U8") (pin "63") (pinfunction "I/O_63") (pintype "passive"))
    )
    (net (code "124") (name "/GPIO65") (class "Default")
      (node (ref "U8") (pin "62") (pinfunction "I/O_62") (pintype "passive"))
    )
    (net (code "125") (name "/GPIO66") (class "Default")
      (node (ref "U8") (pin "61") (pinfunction "I/O_61") (pintype "passive"))
    )
    (net (code "126") (name "/GPIO67") (class "Default")
      (node (ref "U8") (pin "49") (pinfunction "I/O_49") (pintype "passive"))
    )
    (net (code "127") (name "/GPIO68") (class "Default")
      (node (ref "U8") (pin "48") (pinfunction "I/O_48") (pintype "passive"))
    )
    (net (code "128") (name "/GPIO69") (class "Default")
      (node (ref "U8") (pin "47") (pinfunction "I/O_47") (pintype "passive"))
    )
    (net (code "129") (name "/GPIO70") (class "Default")
      (node (ref "U8") (pin "46") (pinfunction "I/O,_GCK1_46") (pintype "passive"))
    )
    (net (code "130") (name "/GPIO71") (class "Default")
      (node (ref "U8") (pin "45") (pinfunction "I/O_45") (pintype "passive"))
    )
    (net (code "131") (name "/GPIO74") (class "Default")
      (node (ref "U8") (pin "39") (pinfunction "I/O_39") (pintype "passive"))
    )
    (net (code "132") (name "/GPIO75") (class "Default")
      (node (ref "U8") (pin "38") (pinfunction "I/O_38") (pintype "passive"))
    )
    (net (code "133") (name "/GPIO76") (class "Default")
      (node (ref "U8") (pin "37") (pinfunction "I/O_37") (pintype "passive"))
    )
    (net (code "134") (name "/GPIO77") (class "Default")
      (node (ref "U8") (pin "36") (pinfunction "I/O_36") (pintype "passive"))
    )
    (net (code "135") (name "/GPIO78") (class "Default")
      (node (ref "U8") (pin "35") (pinfunction "I/O_35") (pintype "passive"))
    )
    (net (code "136") (name "/GPIO79") (class "Default")
      (node (ref "U8") (pin "34") (pinfunction "I/O_34") (pintype "passive"))
    )
    (net (code "137") (name "/GPIO80") (class "Default")
      (node (ref "U8") (pin "23") (pinfunction "I/O_23") (pintype "passive"))
    )
    (net (code "138") (name "/GPIO81") (class "Default")
      (node (ref "U8") (pin "29") (pinfunction "I/O_29") (pintype "passive"))
    )
    (net (code "139") (name "/GPIO82") (class "Default")
      (node (ref "U8") (pin "28") (pinfunction "I/O_28") (pintype "passive"))
    )
    (net (code "140") (name "/GPIO83") (class "Default")
      (node (ref "U8") (pin "22") (pinfunction "I/O_22") (pintype "passive"))
    )
    (net (code "141") (name "/GPIO85") (class "Default")
      (node (ref "U8") (pin "21") (pinfunction "I/O_21") (pintype "passive"))
    )
    (net (code "142") (name "/GPIO86") (class "Default")
      (node (ref "U8") (pin "20") (pinfunction "I/O_20") (pintype "passive"))
    )
    (net (code "143") (name "/GPIO87") (class "Default")
      (node (ref "U8") (pin "19") (pinfunction "I/O_19") (pintype "passive"))
    )
    (net (code "144") (name "/GPIO88") (class "Default")
      (node (ref "U8") (pin "8") (pinfunction "I/O_8") (pintype "passive"))
    )
    (net (code "145") (name "/GPIO89") (class "Default")
      (node (ref "U8") (pin "7") (pinfunction "I/O,_GTS0_7") (pintype "passive"))
    )
    (net (code "146") (name "/GPIO90") (class "Default")
      (node (ref "U8") (pin "6") (pinfunction "I/O_6") (pintype "passive"))
    )
    (net (code "147") (name "/GPIO91") (class "Default")
      (node (ref "U8") (pin "5") (pinfunction "I/O,_GTS3_5") (pintype "passive"))
    )
    (net (code "148") (name "/GPIO92") (class "Default")
      (node (ref "U8") (pin "4") (pinfunction "I/O_4") (pintype "passive"))
    )
    (net (code "149") (name "/GPIO93") (class "Default")
      (node (ref "U8") (pin "3") (pinfunction "I/O,_GTS2_3") (pintype "passive"))
    )
    (net (code "150") (name "/GPIO94") (class "Default")
      (node (ref "U8") (pin "2") (pinfunction "I/O_2") (pintype "passive"))
    )
    (net (code "151") (name "/GPIO99") (class "Default")
      (node (ref "U8") (pin "191") (pinfunction "I/O_191") (pintype "passive"))
    )
    (net (code "152") (name "/GPIO133") (class "Default")
      (node (ref "U8") (pin "56") (pinfunction "I/O_56") (pintype "passive"))
    )
    (net (code "153") (name "/LED1_0_GREEN") (class "Default")
      (node (ref "R39") (pin "1") (pinfunction "1_1") (pintype "passive"))
      (node (ref "U8") (pin "89") (pinfunction "I/O_89") (pintype "passive"))
    )
    (net (code "154") (name "/LED1_0_RED") (class "Default")
      (node (ref "LD4") (pin "8") (pinfunction "A_8") (pintype "passive"))
      (node (ref "U8") (pin "88") (pinfunction "I/O_88") (pintype "passive"))
    )
    (net (code "155") (name "/LED1_1_GREEN") (class "Default")
      (node (ref "R41") (pin "1") (pinfunction "1_1") (pintype "passive"))
      (node (ref "U8") (pin "90") (pinfunction "I/O_90") (pintype "passive"))
    )
    (net (code "156") (name "/LED1_1_RED") (class "Default")
      (node (ref "LD4") (pin "6") (pinfunction "A_6") (pintype "passive"))
      (node (ref "U8") (pin "87") (pinfunction "I/O_87") (pintype "passive"))
    )
    (net (code "157") (name "/LED1_2_GREEN") (class "Default")
      (node (ref "R43") (pin "1") (pinfunction "1_1") (pintype "passive"))
      (node (ref "U8") (pin "91") (pinfunction "I/O_91") (pintype "passive"))
    )
    (net (code "158") (name "/LED1_2_RED") (class "Default")
      (node (ref "LD4") (pin "4") (pinfunction "A_4") (pintype "passive"))
      (node (ref "U8") (pin "86") (pinfunction "I/O_86") (pintype "passive"))
    )
    (net (code "159") (name "/LED1_3_GREEN") (class "Default")
      (node (ref "R45") (pin "1") (pinfunction "1_1") (pintype "passive"))
      (node (ref "U8") (pin "95") (pinfunction "I/O_95") (pintype "passive"))
    )
    (net (code "160") (name "/LED1_3_RED") (class "Default")
      (node (ref "LD4") (pin "2") (pinfunction "A_2") (pintype "passive"))
      (node (ref "U8") (pin "85") (pinfunction "I/O_85") (pintype "passive"))
    )
    (net (code "161") (name "/LED2_0_GREEN") (class "Default")
      (node (ref "R40") (pin "1") (pinfunction "1_1") (pintype "passive"))
      (node (ref "U8") (pin "80") (pinfunction "I/O_80") (pintype "passive"))
    )
    (net (code "162") (name "/LED2_0_RED") (class "Default")
      (node (ref "LD5") (pin "8") (pinfunction "A_8") (pintype "passive"))
      (node (ref "U8") (pin "78") (pinfunction "I/O_78") (pintype "passive"))
    )
    (net (code "163") (name "/LED2_1_GREEN") (class "Default")
      (node (ref "R42") (pin "1") (pinfunction "1_1") (pintype "passive"))
      (node (ref "U8") (pin "82") (pinfunction "I/O_82") (pintype "passive"))
    )
    (net (code "164") (name "/LED2_1_RED") (class "Default")
      (node (ref "LD5") (pin "6") (pinfunction "A_6") (pintype "passive"))
      (node (ref "U8") (pin "77") (pinfunction "I/O_77") (pintype "passive"))
    )
    (net (code "165") (name "/LED2_2_GREEN") (class "Default")
      (node (ref "R44") (pin "1") (pinfunction "1_1") (pintype "passive"))
      (node (ref "U8") (pin "83") (pinfunction "I/O_83") (pintype "passive"))
    )
    (net (code "166") (name "/LED2_2_RED") (class "Default")
      (node (ref "LD5") (pin "4") (pinfunction "A_4") (pintype "passive"))
      (node (ref "U8") (pin "76") (pinfunction "I/O_76") (pintype "passive"))
    )
    (net (code "167") (name "/LED2_3_GREEN") (class "Default")
      (node (ref "R46") (pin "1") (pinfunction "1_1") (pintype "passive"))
      (node (ref "U8") (pin "84") (pinfunction "I/O_84") (pintype "passive"))
    )
    (net (code "168") (name "/LED2_3_RED") (class "Default")
      (node (ref "LD5") (pin "2") (pinfunction "A_2") (pintype "passive"))
      (node (ref "U8") (pin "75") (pinfunction "I/O_75") (pintype "passive"))
    )
    (net (code "169") (name "/PWR_ON_RST") (class "Default")
      (node (ref "U8") (pin "60") (pinfunction "I/O_60") (pintype "passive"))
    )
    (net (code "170") (name "/Push_BT_0") (class "Default")
      (node (ref "C69") (pin "2") (pinfunction "2_2") (pintype "passive"))
      (node (ref "R30") (pin "1") (pinfunction "1_1") (pintype "passive"))
      (node (ref "S2") (pin "2") (pinfunction "2_2") (pintype "passive"))
      (node (ref "U8") (pin "72") (pinfunction "I/O_72") (pintype "passive"))
    )
    (net (code "171") (name "/Push_BT_1") (class "Default")
      (node (ref "C70") (pin "2") (pinfunction "2_2") (pintype "passive"))
      (node (ref "R31") (pin "1") (pinfunction "1_1") (pintype "passive"))
      (node (ref "S3") (pin "2") (pinfunction "2_2") (pintype "passive"))
      (node (ref "U8") (pin "73") (pinfunction "I/O_73") (pintype "passive"))
    )
    (net (code "172") (name "/Push_BT_2") (class "Default")
      (node (ref "C71") (pin "2") (pinfunction "2_2") (pintype "passive"))
      (node (ref "R32") (pin "1") (pinfunction "1_1") (pintype "passive"))
      (node (ref "S4") (pin "2") (pinfunction "2_2") (pintype "passive"))
      (node (ref "U8") (pin "74") (pinfunction "I/O_74") (pintype "passive"))
    )
    (net (code "173") (name "/Spare_0") (class "Default")
      (node (ref "JP5") (pin "2") (pinfunction "2_2") (pintype "passive"))
      (node (ref "U8") (pin "97") (pinfunction "I/O_97") (pintype "passive"))
    )
    (net (code "174") (name "/Spare_1") (class "Default")
      (node (ref "JP6") (pin "2") (pinfunction "2_2") (pintype "passive"))
      (node (ref "U8") (pin "99") (pinfunction "I/O_99") (pintype "passive"))
    )
    (net (code "175") (name "/Spare_2") (class "Default")
      (node (ref "JP7") (pin "2") (pinfunction "2_2") (pintype "passive"))
      (node (ref "U8") (pin "100") (pinfunction "I/O_100") (pintype "passive"))
    )
    (net (code "176") (name "/Spare_3") (class "Default")
      (node (ref "JP8") (pin "2") (pinfunction "2_2") (pintype "passive"))
      (node (ref "U8") (pin "101") (pinfunction "I/O_101") (pintype "passive"))
    )
    (net (code "177") (name "/Spare_4") (class "Default")
      (node (ref "U8") (pin "102") (pinfunction "I/O_102") (pintype "passive"))
    )
    (net (code "178") (name "/Spare_5") (class "Default")
      (node (ref "U8") (pin "103") (pinfunction "I/O_103") (pintype "passive"))
    )
    (net (code "179") (name "/Spare_6") (class "Default")
      (node (ref "U8") (pin "106") (pinfunction "I/O_106") (pintype "passive"))
    )
    (net (code "180") (name "GND_D") (class "Default")
      (node (ref "C69") (pin "1") (pinfunction "1_1") (pintype "passive"))
      (node (ref "C70") (pin "1") (pinfunction "1_1") (pintype "passive"))
      (node (ref "C71") (pin "1") (pinfunction "1_1") (pintype "passive"))
      (node (ref "C72") (pin "1") (pinfunction "1_1") (pintype "passive"))
      (node (ref "C73") (pin "1") (pinfunction "1_1") (pintype "passive"))
      (node (ref "C74") (pin "1") (pinfunction "1_1") (pintype "passive"))
      (node (ref "C75") (pin "1") (pinfunction "1_1") (pintype "passive"))
      (node (ref "C76") (pin "1") (pinfunction "1_1") (pintype "passive"))
      (node (ref "C77") (pin "1") (pinfunction "1_1") (pintype "passive"))
      (node (ref "C78") (pin "1") (pinfunction "1_1") (pintype "passive"))
      (node (ref "C79") (pin "1") (pinfunction "1_1") (pintype "passive"))
      (node (ref "C80") (pin "1") (pinfunction "1_1") (pintype "passive"))
      (node (ref "C81") (pin "1") (pinfunction "1_1") (pintype "passive"))
      (node (ref "C82") (pin "1") (pinfunction "1_1") (pintype "passive"))
      (node (ref "C83") (pin "1") (pinfunction "1_1") (pintype "passive"))
      (node (ref "C84") (pin "1") (pinfunction "1_1") (pintype "passive"))
      (node (ref "C85") (pin "1") (pinfunction "1_1") (pintype "passive"))
      (node (ref "C86") (pin "1") (pinfunction "1_1") (pintype "passive"))
      (node (ref "C87") (pin "1") (pinfunction "1_1") (pintype "passive"))
      (node (ref "J7") (pin "10") (pinfunction "10_10") (pintype "passive"))
      (node (ref "JP10") (pin "1") (pinfunction "1_1") (pintype "passive"))
      (node (ref "JP5") (pin "1") (pinfunction "1_1") (pintype "passive"))
      (node (ref "JP6") (pin "1") (pinfunction "1_1") (pintype "passive"))
      (node (ref "JP7") (pin "1") (pinfunction "1_1") (pintype "passive"))
      (node (ref "JP8") (pin "1") (pinfunction "1_1") (pintype "passive"))
      (node (ref "JP9") (pin "1") (pinfunction "1_1") (pintype "passive"))
      (node (ref "S2") (pin "1") (pinfunction "1_1") (pintype "passive"))
      (node (ref "S3") (pin "1") (pinfunction "1_1") (pintype "passive"))
      (node (ref "S4") (pin "1") (pinfunction "1_1") (pintype "passive"))
      (node (ref "U8") (pin "104") (pinfunction "GND_104") (pintype "passive"))
      (node (ref "U8") (pin "129") (pinfunction "GND_129") (pintype "passive"))
      (node (ref "U8") (pin "13") (pinfunction "GND_13") (pintype "passive"))
      (node (ref "U8") (pin "130") (pinfunction "GND_130") (pintype "passive"))
      (node (ref "U8") (pin "141") (pinfunction "GND_141") (pintype "passive"))
      (node (ref "U8") (pin "156") (pinfunction "GND_156") (pintype "passive"))
      (node (ref "U8") (pin "177") (pinfunction "GND_177") (pintype "passive"))
      (node (ref "U8") (pin "190") (pinfunction "GND_190") (pintype "passive"))
      (node (ref "U8") (pin "207") (pinfunction "GND_207") (pintype "passive"))
      (node (ref "U8") (pin "24") (pinfunction "GND_24") (pintype "passive"))
      (node (ref "U8") (pin "42") (pinfunction "GND_42") (pintype "passive"))
      (node (ref "U8") (pin "52") (pinfunction "GND_52") (pintype "passive"))
      (node (ref "U8") (pin "68") (pinfunction "GND_68") (pintype "passive"))
      (node (ref "U8") (pin "81") (pinfunction "GND_81") (pintype "passive"))
      (node (ref "U8") (pin "93") (pinfunction "GND_93") (pintype "passive"))
    )
    (net (code "181") (name "Net-(JP5-Pad3)") (class "Default")
      (node (ref "JP5") (pin "3") (pinfunction "3_3") (pintype "passive"))
      (node (ref "R33") (pin "1") (pinfunction "1_1") (pintype "passive"))
    )
    (net (code "182") (name "Net-(JP6-Pad3)") (class "Default")
      (node (ref "JP6") (pin "3") (pinfunction "3_3") (pintype "passive"))
      (node (ref "R34") (pin "1") (pinfunction "1_1") (pintype "passive"))
    )
    (net (code "183") (name "Net-(JP7-Pad3)") (class "Default")
      (node (ref "JP7") (pin "3") (pinfunction "3_3") (pintype "passive"))
      (node (ref "R35") (pin "1") (pinfunction "1_1") (pintype "passive"))
    )
    (net (code "184") (name "Net-(JP8-Pad3)") (class "Default")
      (node (ref "JP8") (pin "3") (pinfunction "3_3") (pintype "passive"))
      (node (ref "R36") (pin "1") (pinfunction "1_1") (pintype "passive"))
    )
    (net (code "185") (name "Net-(JP9-Pad3)") (class "Default")
      (node (ref "JP9") (pin "3") (pinfunction "3_3") (pintype "passive"))
      (node (ref "R37") (pin "2") (pinfunction "2_2") (pintype "passive"))
    )
    (net (code "186") (name "Net-(JP10-Pad3)") (class "Default")
      (node (ref "JP10") (pin "3") (pinfunction "3_3") (pintype "passive"))
      (node (ref "R38") (pin "2") (pinfunction "2_2") (pintype "passive"))
    )
    (net (code "187") (name "Net-(LD4-C-Pad1)") (class "Default")
      (node (ref "LD4") (pin "1") (pinfunction "C_1") (pintype "passive"))
      (node (ref "R45") (pin "2") (pinfunction "2_2") (pintype "passive"))
    )
    (net (code "188") (name "Net-(LD4-C-Pad3)") (class "Default")
      (node (ref "LD4") (pin "3") (pinfunction "C_3") (pintype "passive"))
      (node (ref "R43") (pin "2") (pinfunction "2_2") (pintype "passive"))
    )
    (net (code "189") (name "Net-(LD4-C-Pad5)") (class "Default")
      (node (ref "LD4") (pin "5") (pinfunction "C_5") (pintype "passive"))
      (node (ref "R41") (pin "2") (pinfunction "2_2") (pintype "passive"))
    )
    (net (code "190") (name "Net-(LD4-C-Pad7)") (class "Default")
      (node (ref "LD4") (pin "7") (pinfunction "C_7") (pintype "passive"))
      (node (ref "R39") (pin "2") (pinfunction "2_2") (pintype "passive"))
    )
    (net (code "191") (name "Net-(LD5-C-Pad1)") (class "Default")
      (node (ref "LD5") (pin "1") (pinfunction "C_1") (pintype "passive"))
      (node (ref "R46") (pin "2") (pinfunction "2_2") (pintype "passive"))
    )
    (net (code "192") (name "Net-(LD5-C-Pad3)") (class "Default")
      (node (ref "LD5") (pin "3") (pinfunction "C_3") (pintype "passive"))
      (node (ref "R44") (pin "2") (pinfunction "2_2") (pintype "passive"))
    )
    (net (code "193") (name "Net-(LD5-C-Pad5)") (class "Default")
      (node (ref "LD5") (pin "5") (pinfunction "C_5") (pintype "passive"))
      (node (ref "R42") (pin "2") (pinfunction "2_2") (pintype "passive"))
    )
    (net (code "194") (name "Net-(LD5-C-Pad7)") (class "Default")
      (node (ref "LD5") (pin "7") (pinfunction "C_7") (pintype "passive"))
      (node (ref "R40") (pin "2") (pinfunction "2_2") (pintype "passive"))
    )
    (net (code "195") (name "unconnected-(J7-Pad2)") (class "Default")
      (node (ref "J7") (pin "2") (pinfunction "2_2") (pintype "passive+no_connect"))
    )
    (net (code "196") (name "unconnected-(J7-Pad4)") (class "Default")
      (node (ref "J7") (pin "4") (pinfunction "4_4") (pintype "passive+no_connect"))
    )
    (net (code "197") (name "unconnected-(J7-Pad6)") (class "Default")
      (node (ref "J7") (pin "6") (pinfunction "6_6") (pintype "passive+no_connect"))
    )
    (net (code "198") (name "unconnected-(J7-Pad8)") (class "Default")
      (node (ref "J7") (pin "8") (pinfunction "8_8") (pintype "passive+no_connect"))
    )
  )
)
